# sb-mote2.net
KiCad netlist of a schematic drawn in EAGLE
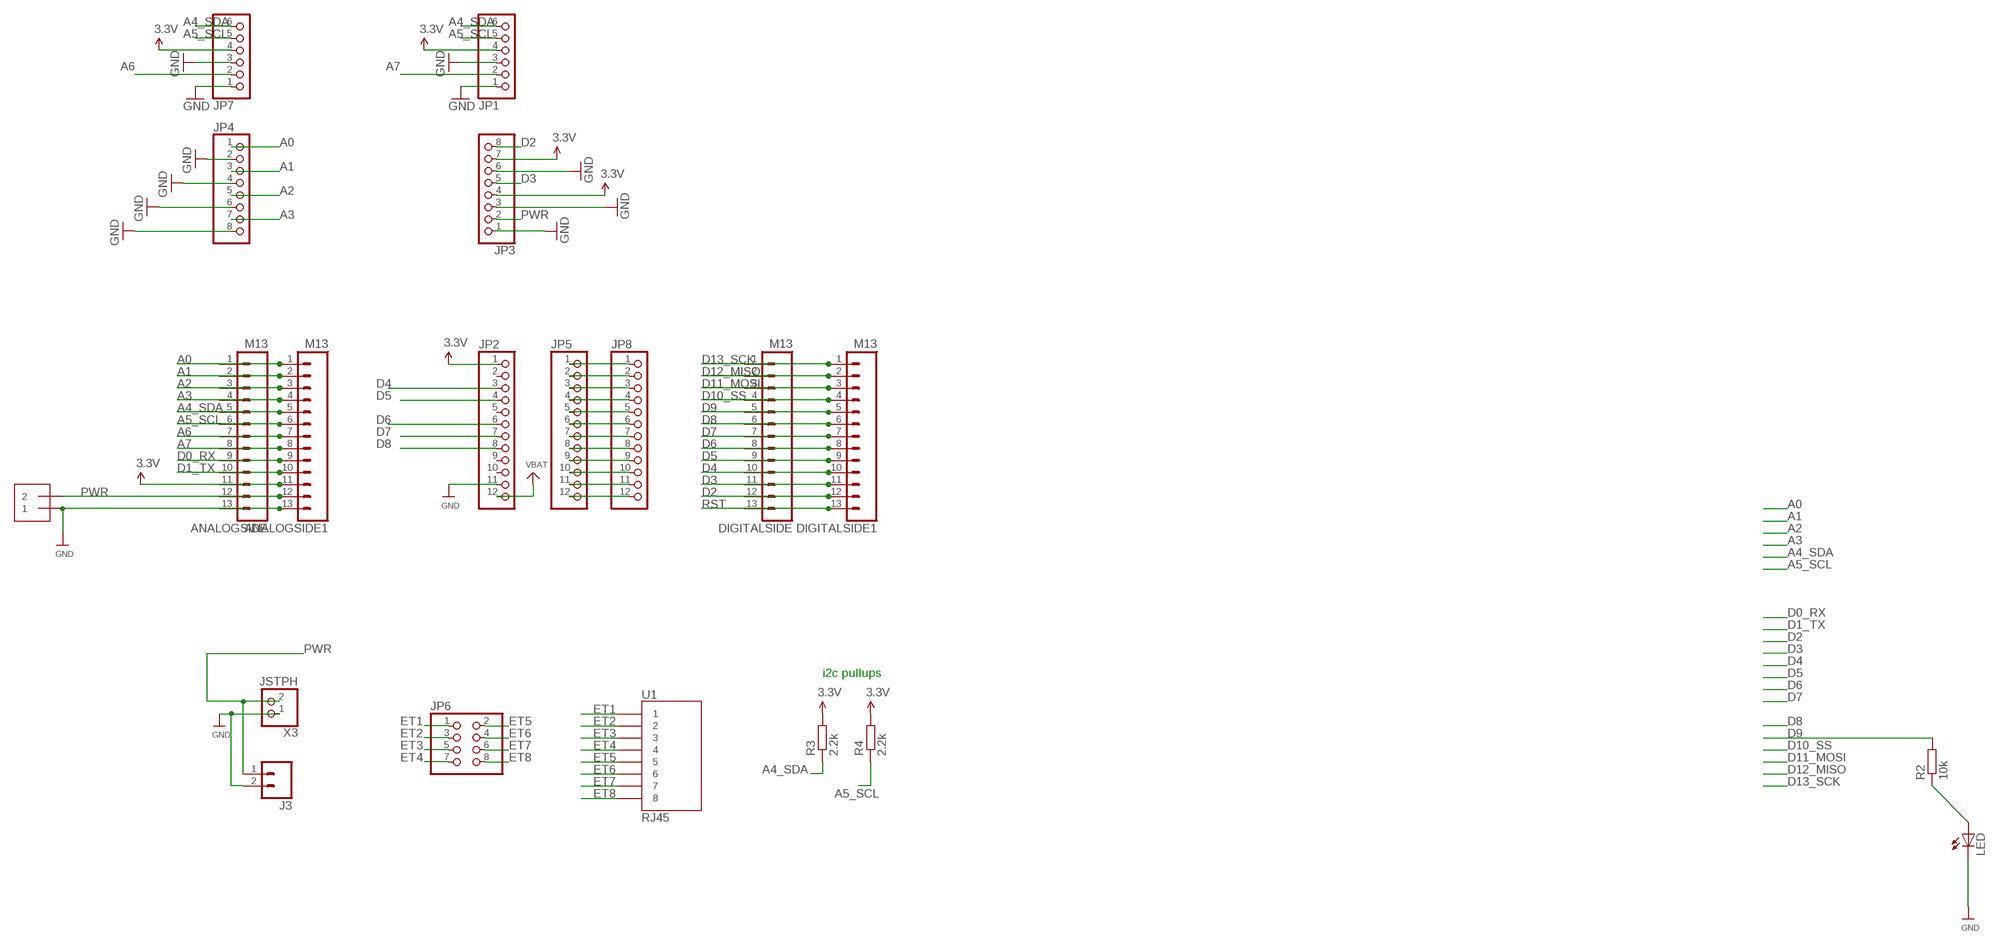
[diagram p0: schematic, sheet 1]

(export (version "E")
  (design (tool "Eeschema 10.0.6"))
  (components
    (comp (ref "ANALOGSIDE")
      (value "M13")
      (footprint "eagle-import:1X13")
      (libsource (lib "eagle-import") (part "M13"))
    )
    (comp (ref "ANALOGSIDE1")
      (value "M13")
      (footprint "eagle-import:1X13")
      (libsource (lib "eagle-import") (part "M13"))
    )
    (comp (ref "DIGITALSIDE")
      (value "M13")
      (footprint "eagle-import:1X13")
      (libsource (lib "eagle-import") (part "M13"))
    )
    (comp (ref "DIGITALSIDE1")
      (value "M13")
      (footprint "eagle-import:1X13")
      (libsource (lib "eagle-import") (part "M13"))
    )
    (comp (ref "J2")
      (value "1X2-3.5MM")
      (footprint "eagle-import:1X2-3.5MM")
      (libsource (lib "eagle-import") (part "1X2-3.5MM"))
    )
    (comp (ref "J3")
      (value "M02PTH")
      (footprint "eagle-import:1X02")
      (libsource (lib "eagle-import") (part "M02PTH"))
    )
    (comp (ref "JP1")
      (value "PINHD-1X6-3.5MM")
      (footprint "eagle-import:1X06-3.5MM")
      (libsource (lib "eagle-import") (part "PINHD-1X6-3.5MM"))
    )
    (comp (ref "JP2")
      (value "PINHD-1X12-CB")
      (footprint "eagle-import:1X12-CB")
      (libsource (lib "eagle-import") (part "PINHD-1X12-CB"))
    )
    (comp (ref "JP3")
      (value "PINHD-1X8-3.5MM")
      (footprint "eagle-import:1X08-3.5MM")
      (libsource (lib "eagle-import") (part "PINHD-1X8-3.5MM"))
    )
    (comp (ref "JP4")
      (value "PINHD-1X8-3.5MM")
      (footprint "eagle-import:1X08-3.5MM")
      (libsource (lib "eagle-import") (part "PINHD-1X8-3.5MM"))
    )
    (comp (ref "JP5")
      (value "PINHD-1X12-CB")
      (footprint "eagle-import:1X12-CB")
      (libsource (lib "eagle-import") (part "PINHD-1X12-CB"))
    )
    (comp (ref "JP6")
      (value "PINHD-2X4")
      (footprint "eagle-import:2X04")
      (libsource (lib "eagle-import") (part "PINHD-2X4"))
    )
    (comp (ref "JP7")
      (value "PINHD-1X6-3.5MM")
      (footprint "eagle-import:1X06-3.5MM")
      (libsource (lib "eagle-import") (part "PINHD-1X6-3.5MM"))
    )
    (comp (ref "JP8")
      (value "PINHD-1X12-CB")
      (footprint "eagle-import:1X12-CB")
      (libsource (lib "eagle-import") (part "PINHD-1X12-CB"))
    )
    (comp (ref "LED")
      (value "LED3MM")
      (footprint "eagle-import:LED3MM")
      (libsource (lib "eagle-import") (part "LED3MM"))
    )
    (comp (ref "R2")
      (value "10k")
      (footprint "eagle-import:0204_7")
      (libsource (lib "eagle-import") (part "R-EU_0204/7"))
    )
    (comp (ref "R3")
      (value "2.2k")
      (footprint "eagle-import:0204_7")
      (libsource (lib "eagle-import") (part "R-EU_0204/7"))
    )
    (comp (ref "R4")
      (value "2.2k")
      (footprint "eagle-import:0204_7")
      (libsource (lib "eagle-import") (part "R-EU_0204/7"))
    )
    (comp (ref "U1")
      (value "RJ45")
      (footprint "eagle-import:RJ45-8")
      (libsource (lib "eagle-import") (part "RJ45-8PTH"))
    )
    (comp (ref "X3")
      (value "JSTPH")
      (footprint "eagle-import:JSTPH2")
      (libsource (lib "eagle-import") (part "CON_JST_PH_2PIN"))
    )
  )
  (nets
    (net (code "1") (name "/A0") (class "Default")
      (node (ref "ANALOGSIDE") (pin "1") (pinfunction "1_1") (pintype "passive"))
      (node (ref "ANALOGSIDE1") (pin "1") (pinfunction "1_1") (pintype "passive"))
      (node (ref "JP4") (pin "1") (pinfunction "1_1") (pintype "passive"))
    )
    (net (code "2") (name "/A1") (class "Default")
      (node (ref "ANALOGSIDE") (pin "2") (pinfunction "2_2") (pintype "passive"))
      (node (ref "ANALOGSIDE1") (pin "2") (pinfunction "2_2") (pintype "passive"))
      (node (ref "JP4") (pin "3") (pinfunction "3_3") (pintype "passive"))
    )
    (net (code "3") (name "/A2") (class "Default")
      (node (ref "ANALOGSIDE") (pin "3") (pinfunction "3_3") (pintype "passive"))
      (node (ref "ANALOGSIDE1") (pin "3") (pinfunction "3_3") (pintype "passive"))
      (node (ref "JP4") (pin "5") (pinfunction "5_5") (pintype "passive"))
    )
    (net (code "4") (name "/A3") (class "Default")
      (node (ref "ANALOGSIDE") (pin "4") (pinfunction "4_4") (pintype "passive"))
      (node (ref "ANALOGSIDE1") (pin "4") (pinfunction "4_4") (pintype "passive"))
      (node (ref "JP4") (pin "7") (pinfunction "7_7") (pintype "passive"))
    )
    (net (code "5") (name "/A4_SDA") (class "Default")
      (node (ref "ANALOGSIDE") (pin "5") (pinfunction "5_5") (pintype "passive"))
      (node (ref "ANALOGSIDE1") (pin "5") (pinfunction "5_5") (pintype "passive"))
      (node (ref "JP1") (pin "6") (pinfunction "6_6") (pintype "passive"))
      (node (ref "JP7") (pin "6") (pinfunction "6_6") (pintype "passive"))
      (node (ref "R3") (pin "1") (pinfunction "1_1") (pintype "passive"))
    )
    (net (code "6") (name "/A5_SCL") (class "Default")
      (node (ref "ANALOGSIDE") (pin "6") (pinfunction "6_6") (pintype "passive"))
      (node (ref "ANALOGSIDE1") (pin "6") (pinfunction "6_6") (pintype "passive"))
      (node (ref "JP1") (pin "5") (pinfunction "5_5") (pintype "passive"))
      (node (ref "JP7") (pin "5") (pinfunction "5_5") (pintype "passive"))
      (node (ref "R4") (pin "1") (pinfunction "1_1") (pintype "passive"))
    )
    (net (code "7") (name "/A6") (class "Default")
      (node (ref "ANALOGSIDE") (pin "7") (pinfunction "7_7") (pintype "passive"))
      (node (ref "ANALOGSIDE1") (pin "7") (pinfunction "7_7") (pintype "passive"))
      (node (ref "JP7") (pin "2") (pinfunction "2_2") (pintype "passive"))
    )
    (net (code "8") (name "/A7") (class "Default")
      (node (ref "ANALOGSIDE") (pin "8") (pinfunction "8_8") (pintype "passive"))
      (node (ref "ANALOGSIDE1") (pin "8") (pinfunction "8_8") (pintype "passive"))
      (node (ref "JP1") (pin "2") (pinfunction "2_2") (pintype "passive"))
    )
    (net (code "9") (name "/D0_RX") (class "Default")
      (node (ref "ANALOGSIDE") (pin "9") (pinfunction "9_9") (pintype "passive"))
      (node (ref "ANALOGSIDE1") (pin "9") (pinfunction "9_9") (pintype "passive"))
    )
    (net (code "10") (name "/D1_TX") (class "Default")
      (node (ref "ANALOGSIDE") (pin "10") (pinfunction "10_10") (pintype "passive"))
      (node (ref "ANALOGSIDE1") (pin "10") (pinfunction "10_10") (pintype "passive"))
    )
    (net (code "11") (name "/D2") (class "Default")
      (node (ref "DIGITALSIDE") (pin "12") (pinfunction "12_12") (pintype "passive"))
      (node (ref "DIGITALSIDE1") (pin "12") (pinfunction "12_12") (pintype "passive"))
      (node (ref "JP3") (pin "8") (pinfunction "8_8") (pintype "passive"))
    )
    (net (code "12") (name "/D3") (class "Default")
      (node (ref "DIGITALSIDE") (pin "11") (pinfunction "11_11") (pintype "passive"))
      (node (ref "DIGITALSIDE1") (pin "11") (pinfunction "11_11") (pintype "passive"))
      (node (ref "JP3") (pin "5") (pinfunction "5_5") (pintype "passive"))
    )
    (net (code "13") (name "/D4") (class "Default")
      (node (ref "DIGITALSIDE") (pin "10") (pinfunction "10_10") (pintype "passive"))
      (node (ref "DIGITALSIDE1") (pin "10") (pinfunction "10_10") (pintype "passive"))
      (node (ref "JP2") (pin "3") (pinfunction "3_3") (pintype "passive"))
    )
    (net (code "14") (name "/D5") (class "Default")
      (node (ref "DIGITALSIDE") (pin "9") (pinfunction "9_9") (pintype "passive"))
      (node (ref "DIGITALSIDE1") (pin "9") (pinfunction "9_9") (pintype "passive"))
      (node (ref "JP2") (pin "4") (pinfunction "4_4") (pintype "passive"))
    )
    (net (code "15") (name "/D6") (class "Default")
      (node (ref "DIGITALSIDE") (pin "8") (pinfunction "8_8") (pintype "passive"))
      (node (ref "DIGITALSIDE1") (pin "8") (pinfunction "8_8") (pintype "passive"))
      (node (ref "JP2") (pin "6") (pinfunction "6_6") (pintype "passive"))
    )
    (net (code "16") (name "/D7") (class "Default")
      (node (ref "DIGITALSIDE") (pin "7") (pinfunction "7_7") (pintype "passive"))
      (node (ref "DIGITALSIDE1") (pin "7") (pinfunction "7_7") (pintype "passive"))
      (node (ref "JP2") (pin "7") (pinfunction "7_7") (pintype "passive"))
    )
    (net (code "17") (name "/D8") (class "Default")
      (node (ref "DIGITALSIDE") (pin "6") (pinfunction "6_6") (pintype "passive"))
      (node (ref "DIGITALSIDE1") (pin "6") (pinfunction "6_6") (pintype "passive"))
      (node (ref "JP2") (pin "8") (pinfunction "8_8") (pintype "passive"))
    )
    (net (code "18") (name "/D9") (class "Default")
      (node (ref "DIGITALSIDE") (pin "5") (pinfunction "5_5") (pintype "passive"))
      (node (ref "DIGITALSIDE1") (pin "5") (pinfunction "5_5") (pintype "passive"))
      (node (ref "R2") (pin "2") (pinfunction "2_2") (pintype "passive"))
    )
    (net (code "19") (name "/D10_SS") (class "Default")
      (node (ref "DIGITALSIDE") (pin "4") (pinfunction "4_4") (pintype "passive"))
      (node (ref "DIGITALSIDE1") (pin "4") (pinfunction "4_4") (pintype "passive"))
    )
    (net (code "20") (name "/D11_MOSI") (class "Default")
      (node (ref "DIGITALSIDE") (pin "3") (pinfunction "3_3") (pintype "passive"))
      (node (ref "DIGITALSIDE1") (pin "3") (pinfunction "3_3") (pintype "passive"))
    )
    (net (code "21") (name "/D12_MISO") (class "Default")
      (node (ref "DIGITALSIDE") (pin "2") (pinfunction "2_2") (pintype "passive"))
      (node (ref "DIGITALSIDE1") (pin "2") (pinfunction "2_2") (pintype "passive"))
    )
    (net (code "22") (name "/D13_SCK") (class "Default")
      (node (ref "DIGITALSIDE") (pin "1") (pinfunction "1_1") (pintype "passive"))
      (node (ref "DIGITALSIDE1") (pin "1") (pinfunction "1_1") (pintype "passive"))
    )
    (net (code "23") (name "/ET1") (class "Default")
      (node (ref "JP6") (pin "1") (pinfunction "1_1") (pintype "passive"))
      (node (ref "U1") (pin "1") (pinfunction "1_1") (pintype "bidirectional"))
    )
    (net (code "24") (name "/ET2") (class "Default")
      (node (ref "JP6") (pin "3") (pinfunction "3_3") (pintype "passive"))
      (node (ref "U1") (pin "2") (pinfunction "2_2") (pintype "bidirectional"))
    )
    (net (code "25") (name "/ET3") (class "Default")
      (node (ref "JP6") (pin "5") (pinfunction "5_5") (pintype "passive"))
      (node (ref "U1") (pin "3") (pinfunction "3_3") (pintype "bidirectional"))
    )
    (net (code "26") (name "/ET4") (class "Default")
      (node (ref "JP6") (pin "7") (pinfunction "7_7") (pintype "passive"))
      (node (ref "U1") (pin "4") (pinfunction "4_4") (pintype "bidirectional"))
    )
    (net (code "27") (name "/ET5") (class "Default")
      (node (ref "JP6") (pin "2") (pinfunction "2_2") (pintype "passive"))
      (node (ref "U1") (pin "5") (pinfunction "5_5") (pintype "bidirectional"))
    )
    (net (code "28") (name "/ET6") (class "Default")
      (node (ref "JP6") (pin "4") (pinfunction "4_4") (pintype "passive"))
      (node (ref "U1") (pin "6") (pinfunction "6_6") (pintype "bidirectional"))
    )
    (net (code "29") (name "/ET7") (class "Default")
      (node (ref "JP6") (pin "6") (pinfunction "6_6") (pintype "passive"))
      (node (ref "U1") (pin "7") (pinfunction "7_7") (pintype "bidirectional"))
    )
    (net (code "30") (name "/ET8") (class "Default")
      (node (ref "JP6") (pin "8") (pinfunction "8_8") (pintype "passive"))
      (node (ref "U1") (pin "8") (pinfunction "8_8") (pintype "bidirectional"))
    )
    (net (code "31") (name "/PWR") (class "Default")
      (node (ref "ANALOGSIDE") (pin "12") (pinfunction "12_12") (pintype "passive"))
      (node (ref "ANALOGSIDE1") (pin "12") (pinfunction "12_12") (pintype "passive"))
      (node (ref "J2") (pin "2") (pinfunction "2_2") (pintype "passive"))
      (node (ref "J3") (pin "1") (pinfunction "1_1") (pintype "passive"))
      (node (ref "JP3") (pin "2") (pinfunction "2_2") (pintype "passive"))
      (node (ref "X3") (pin "2") (pinfunction "2_2") (pintype "passive"))
    )
    (net (code "32") (name "/RST") (class "Default")
      (node (ref "DIGITALSIDE") (pin "13") (pinfunction "13_13") (pintype "passive"))
      (node (ref "DIGITALSIDE1") (pin "13") (pinfunction "13_13") (pintype "passive"))
    )
    (net (code "33") (name "3.3V") (class "Default")
      (node (ref "ANALOGSIDE") (pin "11") (pinfunction "11_11") (pintype "passive"))
      (node (ref "ANALOGSIDE1") (pin "11") (pinfunction "11_11") (pintype "passive"))
      (node (ref "JP1") (pin "4") (pinfunction "4_4") (pintype "passive"))
      (node (ref "JP2") (pin "1") (pinfunction "1_1") (pintype "passive"))
      (node (ref "JP3") (pin "4") (pinfunction "4_4") (pintype "passive"))
      (node (ref "JP3") (pin "7") (pinfunction "7_7") (pintype "passive"))
      (node (ref "JP7") (pin "4") (pinfunction "4_4") (pintype "passive"))
      (node (ref "R3") (pin "2") (pinfunction "2_2") (pintype "passive"))
      (node (ref "R4") (pin "2") (pinfunction "2_2") (pintype "passive"))
    )
    (net (code "34") (name "GND") (class "Default")
      (node (ref "ANALOGSIDE") (pin "13") (pinfunction "13_13") (pintype "passive"))
      (node (ref "ANALOGSIDE1") (pin "13") (pinfunction "13_13") (pintype "passive"))
      (node (ref "J2") (pin "1") (pinfunction "1_1") (pintype "passive"))
      (node (ref "J3") (pin "2") (pinfunction "2_2") (pintype "passive"))
      (node (ref "JP1") (pin "1") (pinfunction "1_1") (pintype "passive"))
      (node (ref "JP1") (pin "3") (pinfunction "3_3") (pintype "passive"))
      (node (ref "JP2") (pin "11") (pinfunction "11_11") (pintype "passive"))
      (node (ref "JP3") (pin "1") (pinfunction "1_1") (pintype "passive"))
      (node (ref "JP3") (pin "3") (pinfunction "3_3") (pintype "passive"))
      (node (ref "JP3") (pin "6") (pinfunction "6_6") (pintype "passive"))
      (node (ref "JP4") (pin "2") (pinfunction "2_2") (pintype "passive"))
      (node (ref "JP4") (pin "4") (pinfunction "4_4") (pintype "passive"))
      (node (ref "JP4") (pin "6") (pinfunction "6_6") (pintype "passive"))
      (node (ref "JP4") (pin "8") (pinfunction "8_8") (pintype "passive"))
      (node (ref "JP7") (pin "1") (pinfunction "1_1") (pintype "passive"))
      (node (ref "JP7") (pin "3") (pinfunction "3_3") (pintype "passive"))
      (node (ref "LED") (pin "K") (pinfunction "C_K") (pintype "passive"))
      (node (ref "X3") (pin "1") (pinfunction "1_1") (pintype "passive"))
    )
    (net (code "35") (name "Net-(JP5-Pad1)") (class "Default")
      (node (ref "JP5") (pin "1") (pinfunction "1_1") (pintype "passive"))
      (node (ref "JP8") (pin "1") (pinfunction "1_1") (pintype "passive"))
    )
    (net (code "36") (name "Net-(JP5-Pad2)") (class "Default")
      (node (ref "JP5") (pin "2") (pinfunction "2_2") (pintype "passive"))
      (node (ref "JP8") (pin "2") (pinfunction "2_2") (pintype "passive"))
    )
    (net (code "37") (name "Net-(JP5-Pad3)") (class "Default")
      (node (ref "JP5") (pin "3") (pinfunction "3_3") (pintype "passive"))
      (node (ref "JP8") (pin "3") (pinfunction "3_3") (pintype "passive"))
    )
    (net (code "38") (name "Net-(JP5-Pad4)") (class "Default")
      (node (ref "JP5") (pin "4") (pinfunction "4_4") (pintype "passive"))
      (node (ref "JP8") (pin "4") (pinfunction "4_4") (pintype "passive"))
    )
    (net (code "39") (name "Net-(JP5-Pad5)") (class "Default")
      (node (ref "JP5") (pin "5") (pinfunction "5_5") (pintype "passive"))
      (node (ref "JP8") (pin "5") (pinfunction "5_5") (pintype "passive"))
    )
    (net (code "40") (name "Net-(JP5-Pad6)") (class "Default")
      (node (ref "JP5") (pin "6") (pinfunction "6_6") (pintype "passive"))
      (node (ref "JP8") (pin "6") (pinfunction "6_6") (pintype "passive"))
    )
    (net (code "41") (name "Net-(JP5-Pad7)") (class "Default")
      (node (ref "JP5") (pin "7") (pinfunction "7_7") (pintype "passive"))
      (node (ref "JP8") (pin "7") (pinfunction "7_7") (pintype "passive"))
    )
    (net (code "42") (name "Net-(JP5-Pad8)") (class "Default")
      (node (ref "JP5") (pin "8") (pinfunction "8_8") (pintype "passive"))
      (node (ref "JP8") (pin "8") (pinfunction "8_8") (pintype "passive"))
    )
    (net (code "43") (name "Net-(JP5-Pad9)") (class "Default")
      (node (ref "JP5") (pin "9") (pinfunction "9_9") (pintype "passive"))
      (node (ref "JP8") (pin "9") (pinfunction "9_9") (pintype "passive"))
    )
    (net (code "44") (name "Net-(JP5-Pad10)") (class "Default")
      (node (ref "JP5") (pin "10") (pinfunction "10_10") (pintype "passive"))
      (node (ref "JP8") (pin "10") (pinfunction "10_10") (pintype "passive"))
    )
    (net (code "45") (name "Net-(JP5-Pad11)") (class "Default")
      (node (ref "JP5") (pin "11") (pinfunction "11_11") (pintype "passive"))
      (node (ref "JP8") (pin "11") (pinfunction "11_11") (pintype "passive"))
    )
    (net (code "46") (name "Net-(JP5-Pad12)") (class "Default")
      (node (ref "JP5") (pin "12") (pinfunction "12_12") (pintype "passive"))
      (node (ref "JP8") (pin "12") (pinfunction "12_12") (pintype "passive"))
    )
    (net (code "47") (name "Net-(LED-PadA)") (class "Default")
      (node (ref "LED") (pin "A") (pinfunction "A_A") (pintype "passive"))
      (node (ref "R2") (pin "1") (pinfunction "1_1") (pintype "passive"))
    )
    (net (code "48") (name "VBAT") (class "Default")
      (node (ref "JP2") (pin "12") (pinfunction "12_12") (pintype "passive"))
    )
    (net (code "49") (name "unconnected-(JP2-Pad2)") (class "Default")
      (node (ref "JP2") (pin "2") (pinfunction "2_2") (pintype "passive"))
    )
    (net (code "50") (name "unconnected-(JP2-Pad5)") (class "Default")
      (node (ref "JP2") (pin "5") (pinfunction "5_5") (pintype "passive"))
    )
    (net (code "51") (name "unconnected-(JP2-Pad9)") (class "Default")
      (node (ref "JP2") (pin "9") (pinfunction "9_9") (pintype "passive"))
    )
    (net (code "52") (name "unconnected-(JP2-Pad10)") (class "Default")
      (node (ref "JP2") (pin "10") (pinfunction "10_10") (pintype "passive"))
    )
  )
)
